# Periphery.net
KiCad netlist of a schematic drawn in Altium Designer
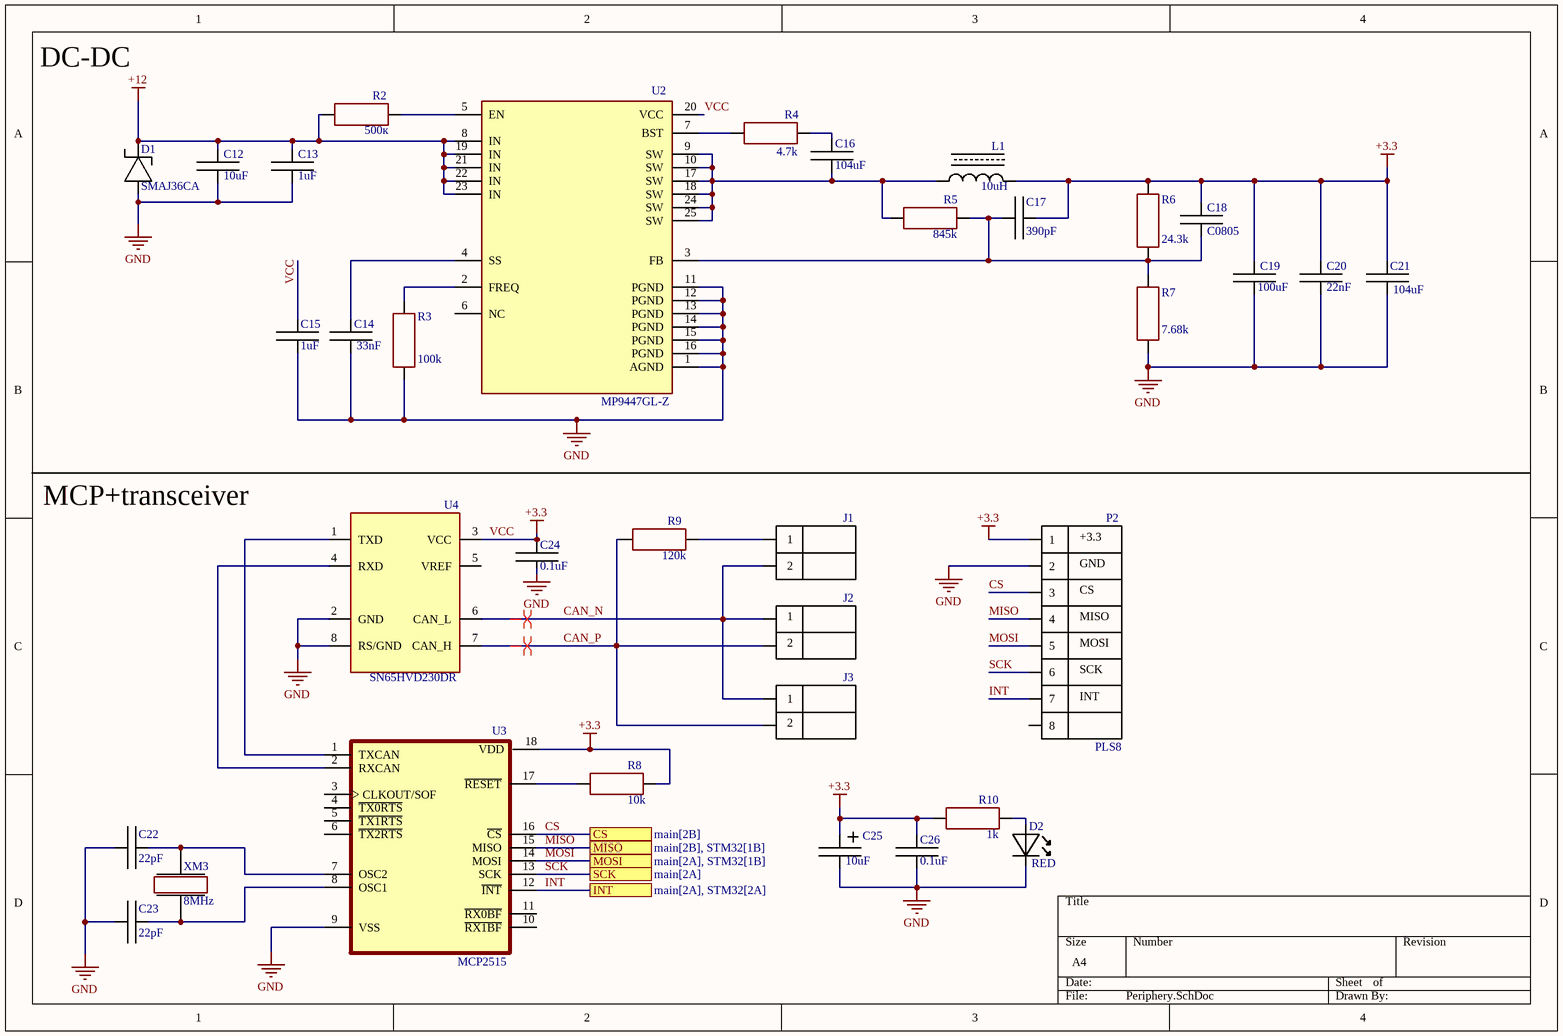
[diagram p0: Periphery.SchDoc]

(export (version "E")
  (design (tool "Eeschema 10.0.6"))
  (components
    (comp (ref "C12")
      (value "10uF")
      (footprint "C0805")
      (description "Керамический конденсатор. 1uF,10uF,106uF,33pF,100uF")
      (libsource (lib "Integrated_Library1") (part "C0805"))
    )
    (comp (ref "C13")
      (value "1uF")
      (footprint "C0805")
      (description "Керамический конденсатор. 1uF,10uF,106uF,33pF,100uF")
      (libsource (lib "Integrated_Library1") (part "C0805"))
    )
    (comp (ref "C15")
      (value "1uF")
      (footprint "C0805")
      (description "Керамический конденсатор. 1uF,10uF,106uF,33pF,100uF")
      (libsource (lib "Integrated_Library1") (part "C0805"))
    )
    (comp (ref "C16")
      (value "104uF")
      (footprint "C0805")
      (description "Керамический конденсатор. 1uF,10uF,106uF,33pF,100uF")
      (libsource (lib "Integrated_Library1") (part "C0805"))
    )
    (comp (ref "C17")
      (value "390pF")
      (footprint "C0805")
      (description "Керамический конденсатор. 1uF,10uF,106uF,33pF,100uF")
      (libsource (lib "Integrated_Library1") (part "C0805"))
    )
    (comp (ref "C18")
      (value "C0805")
      (footprint "C0805")
      (description "Керамический конденсатор. 1uF,10uF,106uF,33pF,100uF")
      (libsource (lib "Integrated_Library1") (part "C0805"))
    )
    (comp (ref "C19")
      (value "100uF")
      (footprint "C0805")
      (description "Керамический конденсатор. 1uF,10uF,106uF,33pF,100uF")
      (libsource (lib "Integrated_Library1") (part "C0805"))
    )
    (comp (ref "C20")
      (value "22nF")
      (footprint "C0805")
      (description "Керамический конденсатор. 1uF,10uF,106uF,33pF,100uF")
      (libsource (lib "") (part "C0805_1"))
    )
    (comp (ref "C21")
      (value "104uF")
      (footprint "C0805")
      (description "Керамический конденсатор. 1uF,10uF,106uF,33pF,100uF")
      (libsource (lib "Integrated_Library1") (part "C0805"))
    )
    (comp (ref "C22")
      (value "22pF")
      (footprint "C0805")
      (description "Керамический конденсатор. 1uF,10uF,106uF,33pF,100uF")
      (libsource (lib "Integrated_Library1") (part "C0805"))
    )
    (comp (ref "C23")
      (value "22pF")
      (footprint "C0805")
      (description "Керамический конденсатор. 1uF,10uF,106uF,33pF,100uF")
      (libsource (lib "Integrated_Library1") (part "C0805"))
    )
    (comp (ref "C24")
      (value "0.1uF")
      (footprint "C0805")
      (description "Керамический конденсатор. 1uF,10uF,106uF,33pF,100uF")
      (libsource (lib "Integrated_Library1") (part "C0805"))
    )
    (comp (ref "C25")
      (value "10uF")
      (footprint "CAP_3.5 (8x12мм)")
      (description "Электролит конденсатор (8x12мм)")
      (libsource (lib "Integrated_Library1") (part "C_3.5"))
    )
    (comp (ref "C26")
      (value "0.1uF")
      (footprint "C0805")
      (description "Керамический конденсатор. 1uF,10uF,106uF,33pF,100uF")
      (libsource (lib "Integrated_Library1") (part "C0805"))
    )
    (comp (ref "D1")
      (value "SMAJ36CA")
      (footprint "SMAJ36CA")
      (libsource (lib "Integrated_Library1") (part "SMAJ36CA"))
    )
    (comp (ref "D2")
      (value "RED")
      (footprint "LED0805")
      (description "SMD 0805")
      (libsource (lib "Integrated_Library1") (part "Led"))
    )
    (comp (ref "J1") (value "PLS2") (libsource (lib "Integrated_Library1") (part "PLS2")))
    (comp (ref "J2") (value "PLS2") (libsource (lib "Integrated_Library1") (part "PLS2")))
    (comp (ref "J3") (value "PLS2") (libsource (lib "Integrated_Library1") (part "PLS2")))
    (comp (ref "L1")
      (value "10uH")
      (footprint "Inductor 10uH 8A")
      (libsource (lib "Integrated_Library1") (part "Inductor SMD"))
    )
    (comp (ref "P2") (value "PLS8") (footprint "PLS8") (libsource (lib "Integrated_Library1") (part "PLS8")))
    (comp (ref "R2")
      (value "500к")
      (footprint "R0805")
      (description "SMD")
      (libsource (lib "") (part "R0805_1"))
    )
    (comp (ref "R3")
      (value "100k")
      (footprint "R0805")
      (description "SMD")
      (libsource (lib "Integrated_Library1") (part "R0805"))
    )
    (comp (ref "R4")
      (value "4.7k")
      (footprint "R0805")
      (description "SMD")
      (libsource (lib "") (part "R0805_1"))
    )
    (comp (ref "R5")
      (value "845k")
      (footprint "R0805")
      (description "SMD")
      (libsource (lib "") (part "R0805_1"))
    )
    (comp (ref "R6")
      (value "24.3k")
      (footprint "R0805")
      (description "SMD")
      (libsource (lib "Integrated_Library1") (part "R0805"))
    )
    (comp (ref "R7")
      (value "7.68k")
      (footprint "R0805")
      (description "SMD")
      (libsource (lib "Integrated_Library1") (part "R0805"))
    )
    (comp (ref "R8")
      (value "10k")
      (footprint "R0805")
      (description "SMD")
      (libsource (lib "") (part "R0805_1"))
    )
    (comp (ref "R9")
      (value "120k")
      (footprint "R0805")
      (description "SMD")
      (libsource (lib "") (part "R0805_1"))
    )
    (comp (ref "R10")
      (value "1k")
      (footprint "R0805")
      (description "SMD")
      (libsource (lib "") (part "R0805_1"))
    )
    (comp (ref "U2")
      (value "MP9447GL-Z")
      (footprint "MP9447GL-Z")
      (libsource (lib "Integrated_Library1") (part "MP9447GL-Z"))
    )
    (comp (ref "U3")
      (value "MCP2515")
      (footprint "MCP2515")
      (description "MCP2515-I/SO")
      (libsource (lib "Integrated_Library1") (part "MCP2515"))
    )
    (comp (ref "U4")
      (value "SN65HVD230DR")
      (footprint "SN65HVD230DR")
      (description "трансивер, 1Мбит/с, 3-3,6ВDC, SO8")
      (libsource (lib "Integrated_Library1") (part "SN65HVD230DR"))
    )
    (comp (ref "XM3")
      (value "8MHz")
      (footprint "Resonator")
      (libsource (lib "Integrated_Library1") (part "Resonator"))
    )
    (comp (ref "С14")
      (value "33nF")
      (footprint "C0805")
      (description "Керамический конденсатор. 1uF,10uF,106uF,33pF,100uF")
      (libsource (lib "Integrated_Library1") (part "C0805"))
    )
  )
  (nets
    (net (code "1") (name "+3.3") (class "Default")
      (node (ref "C15") (pin "2") (pinfunction "2_2") (pintype "passive"))
      (node (ref "C17") (pin "2") (pinfunction "2_2") (pintype "passive"))
      (node (ref "C18") (pin "2") (pinfunction "2_2") (pintype "passive"))
      (node (ref "C19") (pin "2") (pinfunction "2_2") (pintype "passive"))
      (node (ref "C20") (pin "2") (pinfunction "2_2") (pintype "passive"))
      (node (ref "C21") (pin "2") (pinfunction "2_2") (pintype "passive"))
      (node (ref "C24") (pin "2") (pinfunction "2_2") (pintype "passive"))
      (node (ref "C25") (pin "1") (pinfunction "1_1") (pintype "passive"))
      (node (ref "C26") (pin "2") (pinfunction "2_2") (pintype "passive"))
      (node (ref "L1") (pin "1") (pinfunction "1_1") (pintype "passive"))
      (node (ref "P2") (pin "1") (pinfunction "1_1") (pintype "passive"))
      (node (ref "R10") (pin "1") (pinfunction "1_1") (pintype "passive"))
      (node (ref "R6") (pin "2") (pinfunction "2_2") (pintype "passive"))
      (node (ref "R8") (pin "2") (pinfunction "2_2") (pintype "passive"))
      (node (ref "U2") (pin "20") (pinfunction "VCC_20") (pintype "passive"))
      (node (ref "U3") (pin "18") (pinfunction "VDD_18") (pintype "passive"))
      (node (ref "U4") (pin "3") (pinfunction "VCC_3") (pintype "passive"))
    )
    (net (code "2") (name "+12") (class "Default")
      (node (ref "C12") (pin "2") (pinfunction "2_2") (pintype "passive"))
      (node (ref "C13") (pin "2") (pinfunction "2_2") (pintype "passive"))
      (node (ref "D1") (pin "2") (pinfunction "2_2") (pintype "passive"))
      (node (ref "R2") (pin "1") (pinfunction "1_1") (pintype "passive"))
      (node (ref "U2") (pin "19") (pinfunction "IN_19") (pintype "passive"))
      (node (ref "U2") (pin "21") (pinfunction "IN_21") (pintype "passive"))
      (node (ref "U2") (pin "22") (pinfunction "IN_22") (pintype "passive"))
      (node (ref "U2") (pin "23") (pinfunction "IN_23") (pintype "passive"))
      (node (ref "U2") (pin "8") (pinfunction "IN_8") (pintype "passive"))
    )
    (net (code "3") (name "/CAN_N") (class "Default")
      (node (ref "J1") (pin "1") (pinfunction "1_1") (pintype "passive"))
      (node (ref "J2") (pin "2") (pinfunction "2_2") (pintype "passive"))
      (node (ref "J3") (pin "2") (pinfunction "2_2") (pintype "passive"))
      (node (ref "U4") (pin "6") (pinfunction "CAN_L_6") (pintype "passive"))
    )
    (net (code "4") (name "/CAN_P") (class "Default")
      (node (ref "J2") (pin "1") (pinfunction "1_1") (pintype "passive"))
      (node (ref "J3") (pin "1") (pinfunction "1_1") (pintype "passive"))
      (node (ref "R9") (pin "1") (pinfunction "1_1") (pintype "passive"))
      (node (ref "U4") (pin "7") (pinfunction "CAN_H_7") (pintype "passive"))
    )
    (net (code "5") (name "/CS") (class "Default")
      (node (ref "P2") (pin "3") (pinfunction "3_3") (pintype "passive"))
      (node (ref "U3") (pin "16") (pinfunction "~{CS}_16") (pintype "passive"))
    )
    (net (code "6") (name "/INT") (class "Default")
      (node (ref "P2") (pin "7") (pinfunction "7_7") (pintype "passive"))
      (node (ref "U3") (pin "12") (pinfunction "~{INT}_12") (pintype "passive"))
    )
    (net (code "7") (name "/MISO") (class "Default")
      (node (ref "P2") (pin "4") (pinfunction "4_4") (pintype "passive"))
      (node (ref "U3") (pin "15") (pinfunction "MISO_15") (pintype "passive"))
    )
    (net (code "8") (name "/MOSI") (class "Default")
      (node (ref "P2") (pin "5") (pinfunction "5_5") (pintype "passive"))
      (node (ref "U3") (pin "14") (pinfunction "MOSI_14") (pintype "passive"))
    )
    (net (code "9") (name "/SCK") (class "Default")
      (node (ref "P2") (pin "6") (pinfunction "6_6") (pintype "passive"))
      (node (ref "U3") (pin "13") (pinfunction "SCK_13") (pintype "passive"))
    )
    (net (code "10") (name "GND") (class "Default")
      (node (ref "C12") (pin "1") (pinfunction "1_1") (pintype "passive"))
      (node (ref "C13") (pin "1") (pinfunction "1_1") (pintype "passive"))
      (node (ref "C15") (pin "1") (pinfunction "1_1") (pintype "passive"))
      (node (ref "C19") (pin "1") (pinfunction "1_1") (pintype "passive"))
      (node (ref "C20") (pin "1") (pinfunction "1_1") (pintype "passive"))
      (node (ref "C21") (pin "1") (pinfunction "1_1") (pintype "passive"))
      (node (ref "C22") (pin "1") (pinfunction "1_1") (pintype "passive"))
      (node (ref "C23") (pin "1") (pinfunction "1_1") (pintype "passive"))
      (node (ref "C24") (pin "1") (pinfunction "1_1") (pintype "passive"))
      (node (ref "C25") (pin "2") (pinfunction "2_2") (pintype "passive"))
      (node (ref "C26") (pin "1") (pinfunction "1_1") (pintype "passive"))
      (node (ref "D1") (pin "1") (pinfunction "1_1") (pintype "passive"))
      (node (ref "D2") (pin "C") (pinfunction "2_C") (pintype "passive"))
      (node (ref "P2") (pin "2") (pinfunction "2_2") (pintype "passive"))
      (node (ref "R3") (pin "1") (pinfunction "1_1") (pintype "passive"))
      (node (ref "R7") (pin "1") (pinfunction "1_1") (pintype "passive"))
      (node (ref "U2") (pin "1") (pinfunction "AGND_1") (pintype "passive"))
      (node (ref "U2") (pin "11") (pinfunction "PGND_11") (pintype "passive"))
      (node (ref "U2") (pin "12") (pinfunction "PGND_12") (pintype "passive"))
      (node (ref "U2") (pin "13") (pinfunction "PGND_13") (pintype "passive"))
      (node (ref "U2") (pin "14") (pinfunction "PGND_14") (pintype "passive"))
      (node (ref "U2") (pin "15") (pinfunction "PGND_15") (pintype "passive"))
      (node (ref "U2") (pin "16") (pinfunction "PGND_16") (pintype "passive"))
      (node (ref "U3") (pin "9") (pinfunction "VSS_9") (pintype "passive"))
      (node (ref "U4") (pin "2") (pinfunction "GND_2") (pintype "passive"))
      (node (ref "U4") (pin "8") (pinfunction "RS/GND_8") (pintype "passive"))
      (node (ref "С14") (pin "1") (pinfunction "1_1") (pintype "passive"))
    )
    (net (code "11") (name "Net-(C16-Pad1)") (class "Default")
      (node (ref "C16") (pin "1") (pinfunction "1_1") (pintype "passive"))
      (node (ref "L1") (pin "2") (pinfunction "2_2") (pintype "passive"))
      (node (ref "R5") (pin "1") (pinfunction "1_1") (pintype "passive"))
      (node (ref "U2") (pin "10") (pinfunction "SW_10") (pintype "passive"))
      (node (ref "U2") (pin "17") (pinfunction "SW_17") (pintype "passive"))
      (node (ref "U2") (pin "18") (pinfunction "SW_18") (pintype "passive"))
      (node (ref "U2") (pin "24") (pinfunction "SW_24") (pintype "passive"))
      (node (ref "U2") (pin "25") (pinfunction "SW_25") (pintype "passive"))
      (node (ref "U2") (pin "9") (pinfunction "SW_9") (pintype "passive"))
    )
    (net (code "12") (name "Net-(C16-Pad2)") (class "Default")
      (node (ref "C16") (pin "2") (pinfunction "2_2") (pintype "passive"))
      (node (ref "R4") (pin "2") (pinfunction "2_2") (pintype "passive"))
    )
    (net (code "13") (name "Net-(D2-1)") (class "Default")
      (node (ref "D2") (pin "A") (pinfunction "1_A") (pintype "passive"))
      (node (ref "R10") (pin "2") (pinfunction "2_2") (pintype "passive"))
    )
    (net (code "14") (name "Net-(J1-Pad2)") (class "Default")
      (node (ref "J1") (pin "2") (pinfunction "2_2") (pintype "passive"))
      (node (ref "R9") (pin "2") (pinfunction "2_2") (pintype "passive"))
    )
    (net (code "15") (name "Net-(U2-BST)") (class "Default")
      (node (ref "R4") (pin "1") (pinfunction "1_1") (pintype "passive"))
      (node (ref "U2") (pin "7") (pinfunction "BST_7") (pintype "passive"))
    )
    (net (code "16") (name "Net-(U2-EN)") (class "Default")
      (node (ref "R2") (pin "2") (pinfunction "2_2") (pintype "passive"))
      (node (ref "U2") (pin "5") (pinfunction "EN_5") (pintype "passive"))
    )
    (net (code "17") (name "Net-(U2-FB)") (class "Default")
      (node (ref "C17") (pin "1") (pinfunction "1_1") (pintype "passive"))
      (node (ref "C18") (pin "1") (pinfunction "1_1") (pintype "passive"))
      (node (ref "R5") (pin "2") (pinfunction "2_2") (pintype "passive"))
      (node (ref "R6") (pin "1") (pinfunction "1_1") (pintype "passive"))
      (node (ref "R7") (pin "2") (pinfunction "2_2") (pintype "passive"))
      (node (ref "U2") (pin "3") (pinfunction "FB_3") (pintype "passive"))
    )
    (net (code "18") (name "Net-(U2-FREQ)") (class "Default")
      (node (ref "R3") (pin "2") (pinfunction "2_2") (pintype "passive"))
      (node (ref "U2") (pin "2") (pinfunction "FREQ_2") (pintype "passive"))
    )
    (net (code "19") (name "Net-(U2-SS)") (class "Default")
      (node (ref "U2") (pin "4") (pinfunction "SS_4") (pintype "passive"))
      (node (ref "С14") (pin "2") (pinfunction "2_2") (pintype "passive"))
    )
    (net (code "20") (name "Net-(U3-OSC1)") (class "Default")
      (node (ref "C23") (pin "2") (pinfunction "2_2") (pintype "passive"))
      (node (ref "U3") (pin "8") (pinfunction "OSC1_8") (pintype "passive"))
      (node (ref "XM3") (pin "1") (pinfunction "1_1") (pintype "passive"))
    )
    (net (code "21") (name "Net-(U3-OSC2)") (class "Default")
      (node (ref "C22") (pin "2") (pinfunction "2_2") (pintype "passive"))
      (node (ref "U3") (pin "7") (pinfunction "OSC2_7") (pintype "passive"))
      (node (ref "XM3") (pin "2") (pinfunction "2_2") (pintype "passive"))
    )
    (net (code "22") (name "Net-(U3-RXCAN)") (class "Default")
      (node (ref "U3") (pin "2") (pinfunction "RXCAN_2") (pintype "passive"))
      (node (ref "U4") (pin "4") (pinfunction "RXD_4") (pintype "passive"))
    )
    (net (code "23") (name "Net-(U3-TXCAN)") (class "Default")
      (node (ref "U3") (pin "1") (pinfunction "TXCAN_1") (pintype "passive"))
      (node (ref "U4") (pin "1") (pinfunction "TXD_1") (pintype "passive"))
    )
    (net (code "24") (name "Net-(U3-~{RESET})") (class "Default")
      (node (ref "R8") (pin "1") (pinfunction "1_1") (pintype "passive"))
      (node (ref "U3") (pin "17") (pinfunction "~{RESET}_17") (pintype "passive"))
    )
    (net (code "25") (name "unconnected-(P2-Pad8)") (class "Default")
      (node (ref "P2") (pin "8") (pinfunction "8_8") (pintype "passive"))
    )
    (net (code "26") (name "unconnected-(U2-NC-Pad6)") (class "Default")
      (node (ref "U2") (pin "6") (pinfunction "NC_6") (pintype "passive"))
    )
    (net (code "27") (name "unconnected-(U3-CLKOUT{slash}SOF-Pad3)") (class "Default")
      (node (ref "U3") (pin "3") (pinfunction "CLKOUT/SOF_3") (pintype "passive"))
    )
    (net (code "28") (name "unconnected-(U3-~{RX0BF}-Pad11)") (class "Default")
      (node (ref "U3") (pin "11") (pinfunction "~{RX0BF}_11") (pintype "passive"))
    )
    (net (code "29") (name "unconnected-(U3-~{RX1BF}-Pad10)") (class "Default")
      (node (ref "U3") (pin "10") (pinfunction "~{RX1BF}_10") (pintype "passive"))
    )
    (net (code "30") (name "unconnected-(U3-~{TX0RTS}-Pad4)") (class "Default")
      (node (ref "U3") (pin "4") (pinfunction "~{TX0RTS}_4") (pintype "passive"))
    )
    (net (code "31") (name "unconnected-(U3-~{TX1RTS}-Pad5)") (class "Default")
      (node (ref "U3") (pin "5") (pinfunction "~{TX1RTS}_5") (pintype "passive"))
    )
    (net (code "32") (name "unconnected-(U3-~{TX2RTS}-Pad6)") (class "Default")
      (node (ref "U3") (pin "6") (pinfunction "~{TX2RTS}_6") (pintype "passive"))
    )
    (net (code "33") (name "unconnected-(U4-VREF-Pad5)") (class "Default")
      (node (ref "U4") (pin "5") (pinfunction "VREF_5") (pintype "passive"))
    )
  )
)
